# Power_Switch.net
KiCad netlist of a schematic drawn in Altium Designer
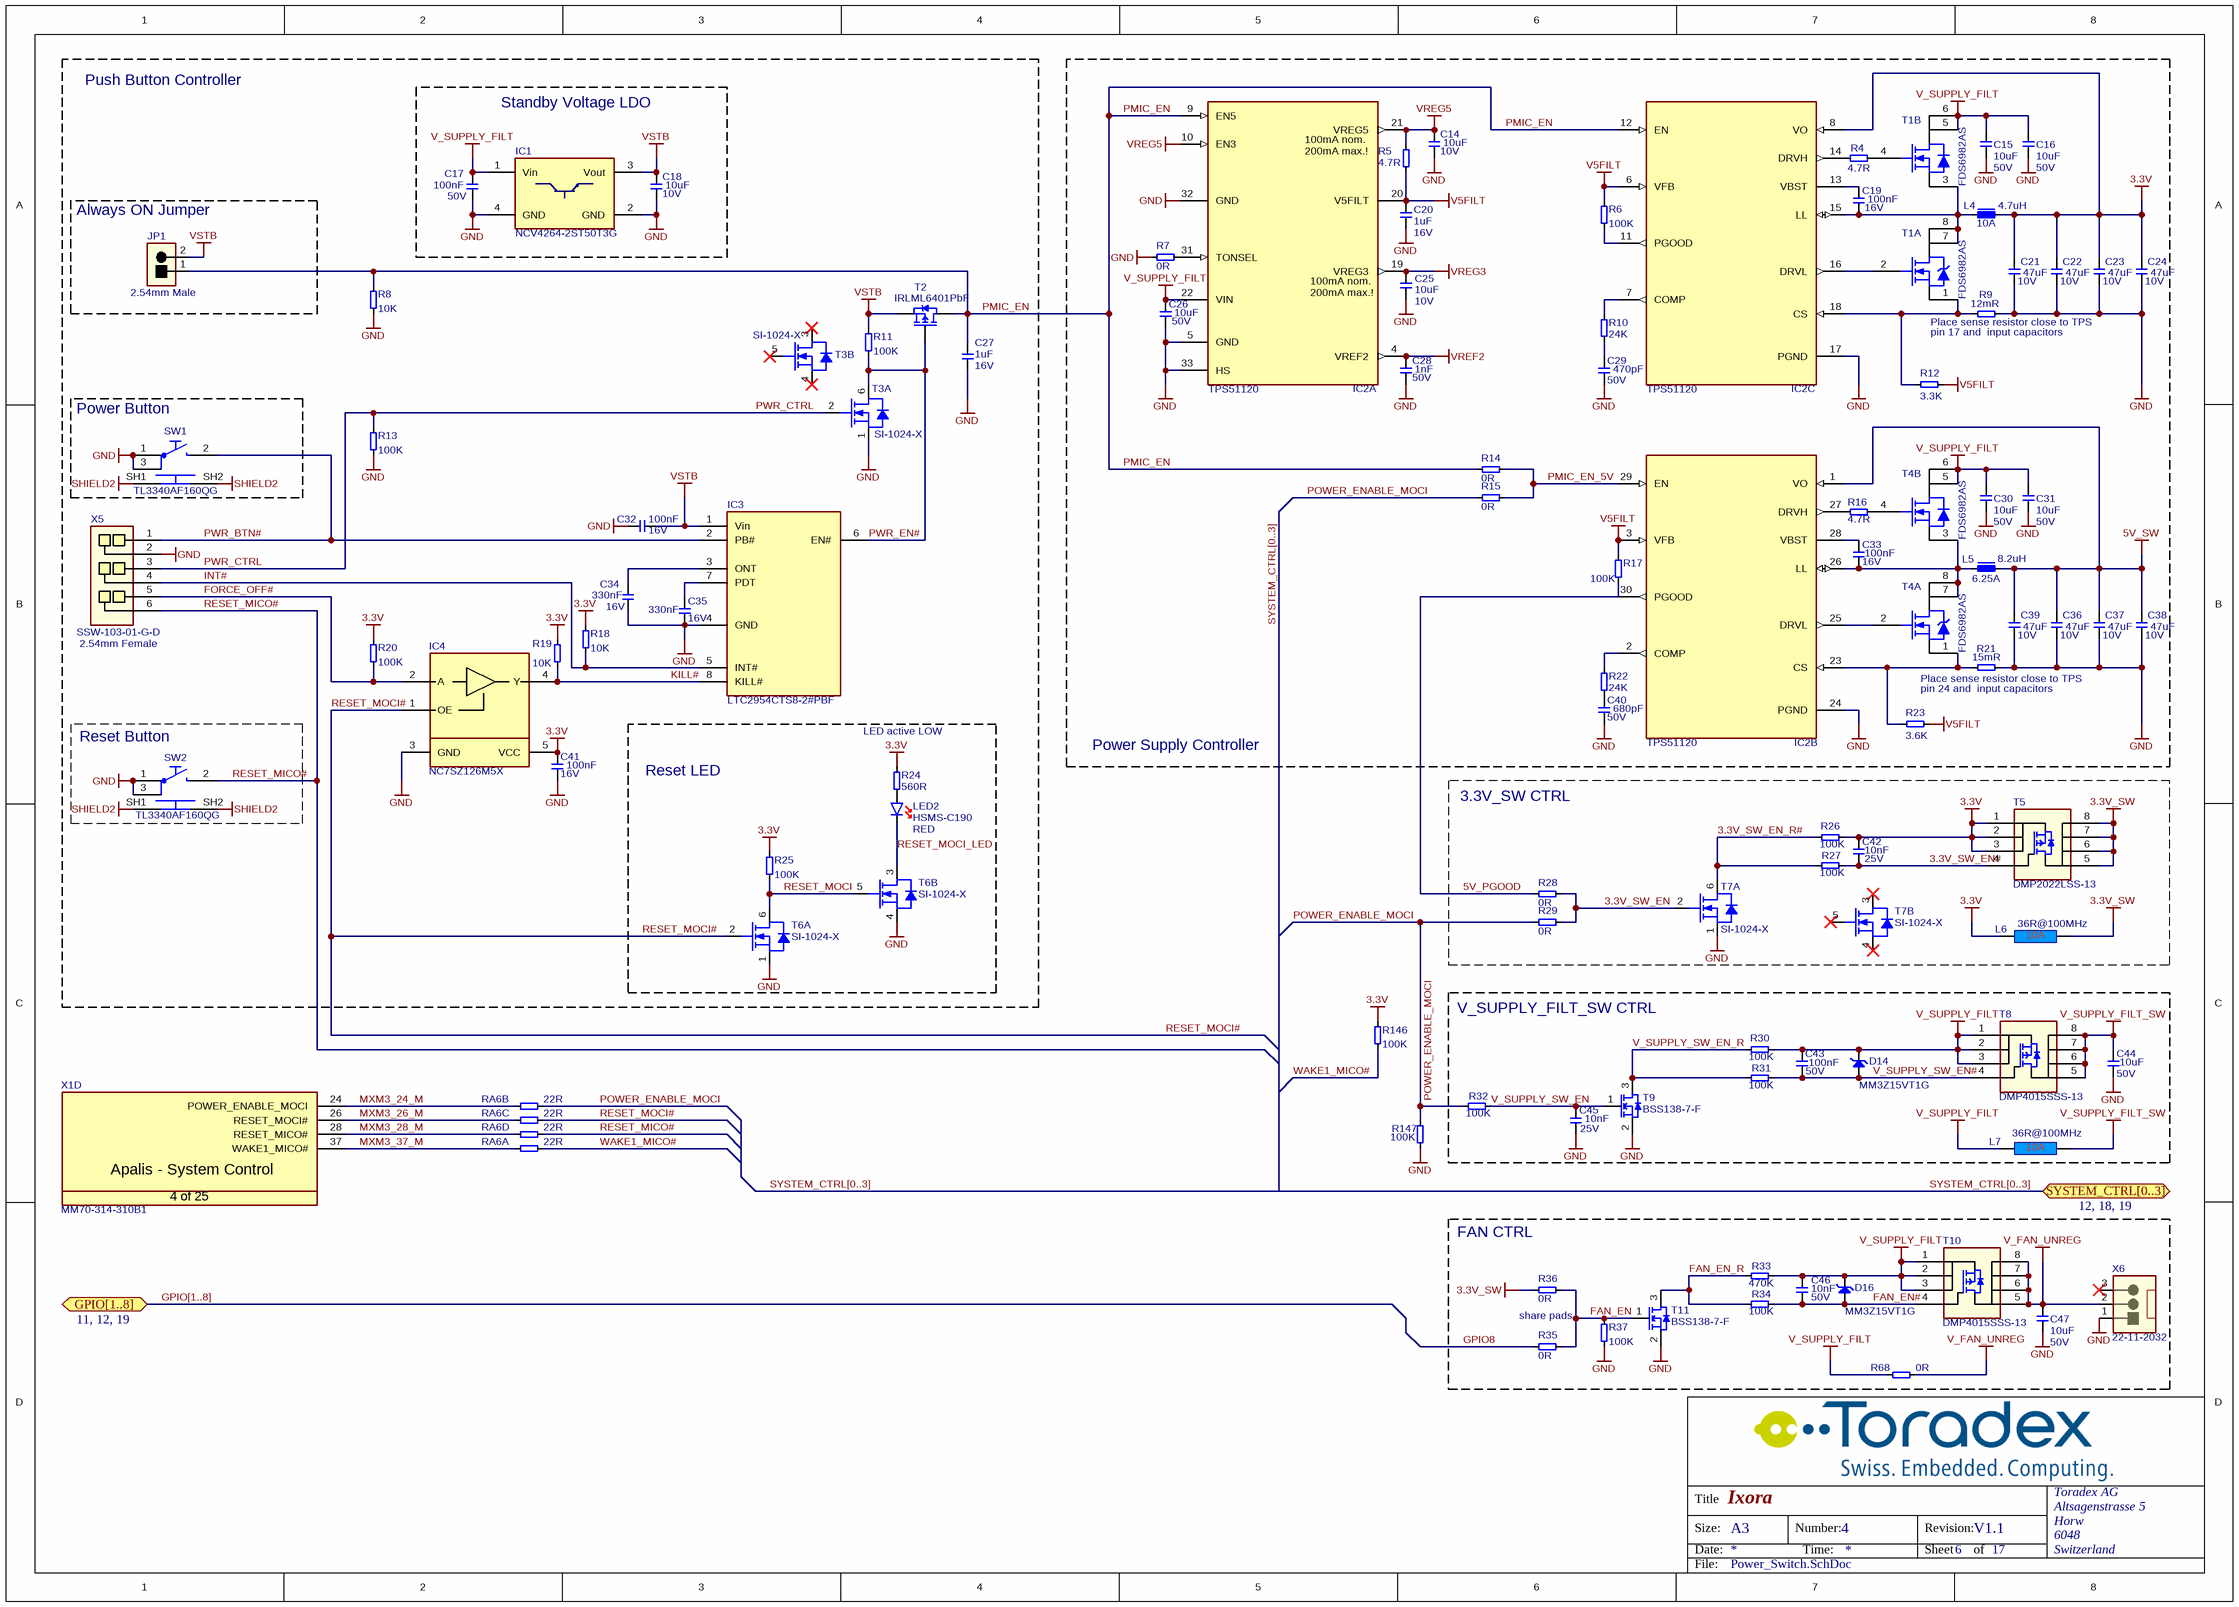
[diagram p0: Power_Switch.SchDoc]

(export (version "E")
  (design (tool "Eeschema 10.0.6"))
  (components
    (comp (ref "C14")
      (value "10uF")
      (footprint "T_CAPC0603X33N")
      (description "Capacitor Ceramic X5R 10uF 10V 20% 0603")
      (fields (field (name "TOLERANCE") "20%") (field (name "RATING") "10V"))
      (libsource (lib "Ixora") (part "C-X5R-10uF-10V-20%-0603"))
    )
    (comp (ref "C15")
      (value "10uF")
      (footprint "CAPC3225X160N")
      (description "Capacitor Ceramic X5R 10uF 50V 20% 1210")
      (fields (field (name "TOLERANCE") "20%") (field (name "RATING") "50V"))
      (libsource (lib "Ixora") (part "C-X5R-10uF-50V-20%-1210"))
    )
    (comp (ref "C16")
      (value "10uF")
      (footprint "CAPC3225X160N")
      (description "Capacitor Ceramic X5R 10uF 50V 20% 1210")
      (fields (field (name "TOLERANCE") "20%") (field (name "RATING") "50V"))
      (libsource (lib "Ixora") (part "C-X5R-10uF-50V-20%-1210"))
    )
    (comp (ref "C17")
      (value "100nF")
      (footprint "T_CAPC0603X33N")
      (description "Capacitor Ceramic X7R 100nF 50V 20% 0603")
      (fields (field (name "TOLERANCE") "20%") (field (name "RATING") "50V"))
      (libsource (lib "Ixora") (part "C-X7R-100nF-50V-20%-0603"))
    )
    (comp (ref "C18")
      (value "10uF")
      (footprint "T_CAPC0603X33N")
      (description "Capacitor Ceramic X5R 10uF 10V 20% 0603")
      (fields (field (name "TOLERANCE") "20%") (field (name "RATING") "10V"))
      (libsource (lib "Ixora") (part "C-X5R-10uF-10V-20%-0603"))
    )
    (comp (ref "C19")
      (value "100nF")
      (footprint "CAPC1005X60N")
      (description "Capacitor Ceramic X7R 100nF 16V 10% 0402")
      (fields (field (name "TOLERANCE") "10%") (field (name "RATING") "16V"))
      (libsource (lib "Ixora") (part "C-X7R-100nF-16V-10%-0402"))
    )
    (comp (ref "C20")
      (value "1uF")
      (footprint "T_CAPC0603X33N")
      (description "Capacitor Ceramic X5R 1uF 16V 20% 0603")
      (fields (field (name "TOLERANCE") "20%") (field (name "RATING") "16V"))
      (libsource (lib "Ixora") (part "C-X5R-1uF-16V-20%-0603"))
    )
    (comp (ref "C21")
      (value "47uF")
      (footprint "T_CAPC0805X125N")
      (description "Capacitor Ceramic X5R 47uF 10V 20% 0805")
      (fields (field (name "TOLERANCE") "20%") (field (name "RATING") "10V"))
      (libsource (lib "Ixora") (part "C-X5R-47uF-10V-20%-0805"))
    )
    (comp (ref "C22")
      (value "47uF")
      (footprint "T_CAPC0805X125N")
      (description "Capacitor Ceramic X5R 47uF 10V 20% 0805")
      (fields (field (name "TOLERANCE") "20%") (field (name "RATING") "10V"))
      (libsource (lib "Ixora") (part "C-X5R-47uF-10V-20%-0805"))
    )
    (comp (ref "C23")
      (value "47uF")
      (footprint "T_CAPC0805X125N")
      (description "Capacitor Ceramic X5R 47uF 10V 20% 0805")
      (fields (field (name "TOLERANCE") "20%") (field (name "RATING") "10V"))
      (libsource (lib "Ixora") (part "C-X5R-47uF-10V-20%-0805"))
    )
    (comp (ref "C24")
      (value "47uF")
      (footprint "T_CAPC0805X125N")
      (description "Capacitor Ceramic X5R 47uF 10V 20% 0805")
      (fields (field (name "TOLERANCE") "20%") (field (name "RATING") "10V"))
      (libsource (lib "Ixora") (part "C-X5R-47uF-10V-20%-0805"))
    )
    (comp (ref "C25")
      (value "10uF")
      (footprint "T_CAPC0603X33N")
      (description "Capacitor Ceramic X5R 10uF 10V 20% 0603")
      (fields (field (name "TOLERANCE") "20%") (field (name "RATING") "10V"))
      (libsource (lib "Ixora") (part "C-X5R-10uF-10V-20%-0603"))
    )
    (comp (ref "C26")
      (value "10uF")
      (footprint "CAPC3225X160N")
      (description "Capacitor Ceramic X5R 10uF 50V 20% 1210")
      (fields (field (name "TOLERANCE") "20%") (field (name "RATING") "50V"))
      (libsource (lib "Ixora") (part "C-X5R-10uF-50V-20%-1210"))
    )
    (comp (ref "C27")
      (value "1uF")
      (footprint "T_CAPC0603X33N")
      (description "Capacitor Ceramic X5R 1uF 16V 20% 0603")
      (fields (field (name "TOLERANCE") "20%") (field (name "RATING") "16V"))
      (libsource (lib "Ixora") (part "C-X5R-1uF-16V-20%-0603"))
    )
    (comp (ref "C28")
      (value "1nF")
      (footprint "CAPC1005X60N")
      (description "Capacitor Ceramic X7R 1nF 50V 10% 0402")
      (fields (field (name "TOLERANCE") "10%") (field (name "RATING") "50V"))
      (libsource (lib "Ixora") (part "C-X7R-1nF-50V-10%-0402"))
    )
    (comp (ref "C29")
      (value "470pF")
      (footprint "CAPC1005X60N")
      (description "Capacitor Ceramic X7R 470pF 50V 10% 0402")
      (fields (field (name "TOLERANCE") "10%") (field (name "RATING") "50V"))
      (libsource (lib "Ixora") (part "C-X7R-470pF-50V-10%-0402"))
    )
    (comp (ref "C30")
      (value "10uF")
      (footprint "CAPC3225X160N")
      (description "Capacitor Ceramic X5R 10uF 50V 20% 1210")
      (fields (field (name "TOLERANCE") "20%") (field (name "RATING") "50V"))
      (libsource (lib "Ixora") (part "C-X5R-10uF-50V-20%-1210"))
    )
    (comp (ref "C31")
      (value "10uF")
      (footprint "CAPC3225X160N")
      (description "Capacitor Ceramic X5R 10uF 50V 20% 1210")
      (fields (field (name "TOLERANCE") "20%") (field (name "RATING") "50V"))
      (libsource (lib "Ixora") (part "C-X5R-10uF-50V-20%-1210"))
    )
    (comp (ref "C32")
      (value "100nF")
      (footprint "CAPC1005X60N")
      (description "Capacitor Ceramic X7R 100nF 16V 10% 0402")
      (fields (field (name "TOLERANCE") "10%") (field (name "RATING") "16V"))
      (libsource (lib "Ixora") (part "C-X7R-100nF-16V-10%-0402"))
    )
    (comp (ref "C33")
      (value "100nF")
      (footprint "CAPC1005X60N")
      (description "Capacitor Ceramic X7R 100nF 16V 10% 0402")
      (fields (field (name "TOLERANCE") "10%") (field (name "RATING") "16V"))
      (libsource (lib "Ixora") (part "C-X7R-100nF-16V-10%-0402"))
    )
    (comp (ref "C34")
      (value "330nF")
      (footprint "T_CAPC0805X125N")
      (description "Capacitor Ceramic X7R 330nF 16V 10% 0805")
      (fields (field (name "TOLERANCE") "10%") (field (name "RATING") "16V"))
      (libsource (lib "Ixora") (part "C-X7R-330nF-16V-10%-0805"))
    )
    (comp (ref "C35")
      (value "330nF")
      (footprint "T_CAPC0805X125N")
      (description "Capacitor Ceramic X7R 330nF 16V 10% 0805")
      (fields (field (name "TOLERANCE") "10%") (field (name "RATING") "16V"))
      (libsource (lib "Ixora") (part "C-X7R-330nF-16V-10%-0805"))
    )
    (comp (ref "C36")
      (value "47uF")
      (footprint "T_CAPC0805X125N")
      (description "Capacitor Ceramic X5R 47uF 10V 20% 0805")
      (fields (field (name "TOLERANCE") "20%") (field (name "RATING") "10V"))
      (libsource (lib "Ixora") (part "C-X5R-47uF-10V-20%-0805"))
    )
    (comp (ref "C37")
      (value "47uF")
      (footprint "T_CAPC0805X125N")
      (description "Capacitor Ceramic X5R 47uF 10V 20% 0805")
      (fields (field (name "TOLERANCE") "20%") (field (name "RATING") "10V"))
      (libsource (lib "Ixora") (part "C-X5R-47uF-10V-20%-0805"))
    )
    (comp (ref "C38")
      (value "47uF")
      (footprint "T_CAPC0805X125N")
      (description "Capacitor Ceramic X5R 47uF 10V 20% 0805")
      (fields (field (name "TOLERANCE") "20%") (field (name "RATING") "10V"))
      (libsource (lib "Ixora") (part "C-X5R-47uF-10V-20%-0805"))
    )
    (comp (ref "C39")
      (value "47uF")
      (footprint "T_CAPC0805X125N")
      (description "Capacitor Ceramic X5R 47uF 10V 20% 0805")
      (fields (field (name "TOLERANCE") "20%") (field (name "RATING") "10V"))
      (libsource (lib "Ixora") (part "C-X5R-47uF-10V-20%-0805"))
    )
    (comp (ref "C40")
      (value "680pF")
      (footprint "CAPC1005X60N")
      (description "Capacitor Ceramic X7R 680pF 50V 10% 0402")
      (fields (field (name "TOLERANCE") "10%") (field (name "RATING") "50V"))
      (libsource (lib "Ixora") (part "C-X7R-680pF-50V-10%-0402"))
    )
    (comp (ref "C41")
      (value "100nF")
      (footprint "CAPC1005X60N")
      (description "Capacitor Ceramic X7R 100nF 16V 10% 0402")
      (fields (field (name "TOLERANCE") "10%") (field (name "RATING") "16V"))
      (libsource (lib "Ixora") (part "C-X7R-100nF-16V-10%-0402"))
    )
    (comp (ref "C42")
      (value "10nF")
      (footprint "CAPC1005X60N")
      (description "Capacitor Ceramic X7R 10nF 25V 10% 0402")
      (fields (field (name "TOLERANCE") "10%") (field (name "RATING") "25V"))
      (libsource (lib "Ixora") (part "C-X7R-10nF-25V-10%-0402"))
    )
    (comp (ref "C43")
      (value "100nF")
      (footprint "T_CAPC0603X33N")
      (description "Capacitor Ceramic X7R 100nF 50V 20% 0603")
      (fields (field (name "TOLERANCE") "20%") (field (name "RATING") "50V"))
      (libsource (lib "Ixora") (part "C-X7R-100nF-50V-20%-0603"))
    )
    (comp (ref "C44")
      (value "10uF")
      (footprint "CAPC3225X160N")
      (description "Capacitor Ceramic X5R 10uF 50V 20% 1210")
      (fields (field (name "TOLERANCE") "20%") (field (name "RATING") "50V"))
      (libsource (lib "Ixora") (part "C-X5R-10uF-50V-20%-1210"))
    )
    (comp (ref "C45")
      (value "10nF")
      (footprint "CAPC1005X60N")
      (description "Capacitor Ceramic X7R 10nF 25V 10% 0402")
      (fields (field (name "TOLERANCE") "10%") (field (name "RATING") "25V"))
      (libsource (lib "Ixora") (part "C-X7R-10nF-25V-10%-0402"))
    )
    (comp (ref "C46")
      (value "10nF")
      (footprint "CAPC1005X60N")
      (description "Capacitor Ceramic X7R 10nF 50V 10% 0402")
      (fields (field (name "TOLERANCE") "10%") (field (name "RATING") "50V"))
      (libsource (lib "Ixora") (part "C-X7R-10nF-50V-10%-0402"))
    )
    (comp (ref "C47")
      (value "10uF")
      (footprint "CAPC3225X160N")
      (description "Capacitor Ceramic X5R 10uF 50V 20% 1210")
      (fields (field (name "TOLERANCE") "20%") (field (name "RATING") "50V"))
      (libsource (lib "Ixora") (part "C-X5R-10uF-50V-20%-1210"))
    )
    (comp (ref "D14")
      (value "MM3Z15VT1G")
      (footprint "T_SOD-323")
      (description "Zener Diode, Vz=15V, 300mW, SOD-323")
      (fields (field (name "MANUFACTURER PART NO.") "MM3Z15VT1G"))
      (libsource (lib "Ixora") (part "D-OnSemi-MM3Z15VT1G"))
    )
    (comp (ref "D16")
      (value "MM3Z15VT1G")
      (footprint "T_SOD-323")
      (description "Zener Diode, Vz=15V, 300mW, SOD-323")
      (fields (field (name "MANUFACTURER PART NO.") "MM3Z15VT1G"))
      (libsource (lib "Ixora") (part "D-OnSemi-MM3Z15VT1G"))
    )
    (comp (ref "IC1")
      (value "NCV4264-2ST50T3G")
      (footprint "T_ON_NCV4264-2ST50T3G")
      (description "NCV4264-2ST50T3G LDO Regulator")
      (fields (field (name "MANUFACTURER PART NO.") "NCV4264-2ST50T3G"))
      (libsource (lib "Ixora") (part "IC-ON-NCV4264-2ST50T3G"))
    )
    (comp (ref "IC2")
      (value "TPS51120")
      (footprint "QFN50P500X500X100-33N")
      (description "Power Supply Controller")
      (fields (field (name "MANUFACTURER PART NO.") "TPS51120"))
      (libsource (lib "Ixora") (part "IC-TI-TPS51120"))
    )
    (comp (ref "IC3")
      (value "LTC2954CTS8-2#PBF")
      (footprint "T_LINEAR_LTC2954CTS8-2#PBF")
      (description "Push Button On/Off Controller")
      (fields (field (name "MANUFACTURER PART NO.") "LTC2954CTS8-2#PBF"))
      (libsource (lib "Ixora") (part "IC-LIN-LTC2954CTS8-2#PBF"))
    )
    (comp (ref "IC4")
      (value "NC7SZ126M5X")
      (footprint "SOT95P279X142-5N")
      (description "NC7SZ126M5X  Buffer Three-State Output")
      (fields (field (name "MANUFACTURER PART NO.") "NC7SZ126M5X"))
      (libsource (lib "Ixora") (part "IC-FAR-NC7SZ126M5X"))
    )
    (comp (ref "JP1")
      (value "TSW-101-07-G-D")
      (footprint "T_Samtec_TSW-101-07-G-D")
      (description "Header male, 1x2 Pins, 2.54 mm pitch")
      (libsource (lib "Ixora") (part "CON-Samtec-TSW-101-07-G-D"))
    )
    (comp (ref "L4")
      (value "4.7uH")
      (footprint "T_INDM110100")
      (description "Inductance 4.7uH 10A 20% 15.5 mOhm -40°C to125°C")
      (fields
        (field (name "TOLERANCE") "20%")
        (field (name "MANUFACTURER PART NO.") "SRP1038A-4R7M")
        (field (name "RATING") "10A")
      )
      (libsource (lib "Ixora") (part "L-Bourns-SRP1038A-4R7M"))
    )
    (comp (ref "L5")
      (value "8.2uH")
      (footprint "T_INDM120120X80N")
      (description "Inductance 8.2uH 6.25A 20%")
      (fields
        (field (name "TOLERANCE") "20%")
        (field (name "MANUFACTURER PART NO.") "744771008")
        (field (name "RATING") "6.25A")
      )
      (libsource (lib "Ixora") (part "L-Wurth-744771008-8.2uH-6.25A-20%"))
    )
    (comp (ref "L6")
      (value "36R@100MHz")
      (footprint "T_Laird_35F0121-0SR-10")
      (description "Power Supply FB 10A")
      (fields (field (name "TOLERANCE") "25%"))
      (libsource (lib "Ixora") (part "L-Laird-35F0121-0SR-10-10A-25%"))
    )
    (comp (ref "L7")
      (value "36R@100MHz")
      (footprint "T_Laird_35F0121-0SR-10")
      (description "Power Supply FB 10A")
      (fields (field (name "TOLERANCE") "25%"))
      (libsource (lib "Ixora") (part "L-Laird-35F0121-0SR-10-10A-25%"))
    )
    (comp (ref "LED2")
      (value "LED")
      (footprint "LEDC1608X80N_R")
      (description "Surface mount LED red 20mA")
      (fields (field (name "MANUFACTURER PART NO.") "HSMS-C190") (field (name "COLOR") "RED"))
      (libsource (lib "Ixora") (part "LED-Avago-HSMS-C190"))
    )
    (comp (ref "R4")
      (value "4.7R")
      (footprint "RESC1005X40N")
      (description "Resistor 4.7 ohm 63mW 5% 0402")
      (fields (field (name "TOLERANCE") "5%"))
      (libsource (lib "Ixora") (part "R-4.7R-63mW-5%-0402"))
    )
    (comp (ref "R5")
      (value "4.7R")
      (footprint "RESC1005X40N")
      (description "Resistor 4.7 ohm 63mW 5% 0402")
      (fields (field (name "TOLERANCE") "5%"))
      (libsource (lib "Ixora") (part "R-4.7R-63mW-5%-0402"))
    )
    (comp (ref "R6")
      (value "100K")
      (footprint "RESC1005X40N")
      (description "Resistor 100 Kohm 63mW 5% 0402")
      (fields (field (name "TOLERANCE") "5%"))
      (libsource (lib "Ixora") (part "R-100KR-63mW-5%-0402"))
    )
    (comp (ref "R7")
      (value "0R")
      (footprint "RESC1005X40N")
      (description "Resistor 0 ohm 63mW 1% 0402")
      (fields (field (name "TOLERANCE") "1%"))
      (libsource (lib "Ixora") (part "R-0R-63mW-1%-0402"))
    )
    (comp (ref "R8")
      (value "10K")
      (footprint "RESC1005X40N")
      (description "Resistor 10 Kohm 63mW 5% 0402")
      (fields (field (name "TOLERANCE") "5%"))
      (libsource (lib "Ixora") (part "R-10KR-63mW-5%-0402"))
    )
    (comp (ref "R9")
      (value "12mR")
      (footprint "RESC3316X76N")
      (description "Resistor 12 mohm 250mW 1% 1206")
      (fields (field (name "TOLERANCE") "1%"))
      (libsource (lib "Ixora") (part "R-12mR-250mW-1%-1206"))
    )
    (comp (ref "R10")
      (value "24K")
      (footprint "RESC1005X40N")
      (description "Resistor 24 Kohm 63mW 1% 0402")
      (fields (field (name "TOLERANCE") "1%"))
      (libsource (lib "Ixora") (part "R-24KR-63mW-1%-0402"))
    )
    (comp (ref "R11")
      (value "100K")
      (footprint "RESC1005X40N")
      (description "Resistor 100 Kohm 63mW 5% 0402")
      (fields (field (name "TOLERANCE") "5%"))
      (libsource (lib "Ixora") (part "R-100KR-63mW-5%-0402"))
    )
    (comp (ref "R12")
      (value "3.3K")
      (footprint "RESC1005X40N")
      (description "Resistor 3.3 Kohm 63mW 1% 0402")
      (fields (field (name "TOLERANCE") "1%"))
      (libsource (lib "Ixora") (part "R-3.3KR-63mW-1%-0402"))
    )
    (comp (ref "R13")
      (value "100K")
      (footprint "RESC1005X40N")
      (description "Resistor 100 Kohm 63mW 5% 0402")
      (fields (field (name "TOLERANCE") "5%"))
      (libsource (lib "Ixora") (part "R-100KR-63mW-5%-0402"))
    )
    (comp (ref "R14")
      (value "0R")
      (footprint "T_RESC0603X30N")
      (description "Resistor 0 ohm 63mW 1% 0603")
      (fields (field (name "TOLERANCE") "1%"))
      (libsource (lib "Ixora") (part "R-0R-63mW-1%-0603"))
    )
    (comp (ref "R15")
      (value "0R")
      (footprint "T_RESC0603X30N")
      (description "Resistor 0 ohm 63mW 1% 0603")
      (fields (field (name "TOLERANCE") "1%"))
      (libsource (lib "Ixora") (part "R-0R-63mW-1%-0603"))
    )
    (comp (ref "R16")
      (value "4.7R")
      (footprint "RESC1005X40N")
      (description "Resistor 4.7 ohm 63mW 5% 0402")
      (fields (field (name "TOLERANCE") "5%"))
      (libsource (lib "Ixora") (part "R-4.7R-63mW-5%-0402"))
    )
    (comp (ref "R17")
      (value "100K")
      (footprint "RESC1005X40N")
      (description "Resistor 100 Kohm 63mW 5% 0402")
      (fields (field (name "TOLERANCE") "5%"))
      (libsource (lib "Ixora") (part "R-100KR-63mW-5%-0402"))
    )
    (comp (ref "R18")
      (value "10K")
      (footprint "RESC1005X40N")
      (description "Resistor 10 Kohm 63mW 5% 0402")
      (fields (field (name "TOLERANCE") "5%"))
      (libsource (lib "Ixora") (part "R-10KR-63mW-5%-0402"))
    )
    (comp (ref "R19")
      (value "10K")
      (footprint "RESC1005X40N")
      (description "Resistor 10 Kohm 63mW 5% 0402")
      (fields (field (name "TOLERANCE") "5%"))
      (libsource (lib "Ixora") (part "R-10KR-63mW-5%-0402"))
    )
    (comp (ref "R20")
      (value "100K")
      (footprint "RESC1005X40N")
      (description "Resistor 100 Kohm 63mW 5% 0402")
      (fields (field (name "TOLERANCE") "5%"))
      (libsource (lib "Ixora") (part "R-100KR-63mW-5%-0402"))
    )
    (comp (ref "R21")
      (value "15mR")
      (footprint "RESC3316X76N")
      (description "Resistor 15 mohm 250mW 1% 1206")
      (fields (field (name "TOLERANCE") "1%"))
      (libsource (lib "Ixora") (part "R-15mR-250mW-1%-1206"))
    )
    (comp (ref "R22")
      (value "24K")
      (footprint "RESC1005X40N")
      (description "Resistor 24 Kohm 63mW 1% 0402")
      (fields (field (name "TOLERANCE") "1%"))
      (libsource (lib "Ixora") (part "R-24KR-63mW-1%-0402"))
    )
    (comp (ref "R23")
      (value "3.6K")
      (footprint "RESC1005X40N")
      (description "Resistor 3.6 Kohm 63mW 1% 0402")
      (fields (field (name "TOLERANCE") "1%"))
      (libsource (lib "Ixora") (part "R-3.6KR-63mW-1%-0402"))
    )
    (comp (ref "R24")
      (value "560R")
      (footprint "RESC1005X40N")
      (description "Resistor 560 ohm 63mW 5% 0402")
      (fields (field (name "TOLERANCE") "5%"))
      (libsource (lib "Ixora") (part "R-560R-63mW-5%-0402"))
    )
    (comp (ref "R25")
      (value "100K")
      (footprint "RESC1005X40N")
      (description "Resistor 100 Kohm 63mW 5% 0402")
      (fields (field (name "TOLERANCE") "5%"))
      (libsource (lib "Ixora") (part "R-100KR-63mW-5%-0402"))
    )
    (comp (ref "R26")
      (value "100K")
      (footprint "RESC1005X40N")
      (description "Resistor 100 Kohm 63mW 5% 0402")
      (fields (field (name "TOLERANCE") "5%"))
      (libsource (lib "Ixora") (part "R-100KR-63mW-5%-0402"))
    )
    (comp (ref "R27")
      (value "100K")
      (footprint "RESC1005X40N")
      (description "Resistor 100 Kohm 63mW 5% 0402")
      (fields (field (name "TOLERANCE") "5%"))
      (libsource (lib "Ixora") (part "R-100KR-63mW-5%-0402"))
    )
    (comp (ref "R28")
      (value "0R")
      (footprint "T_RESC0603X30N")
      (description "Resistor 0 ohm 63mW 1% 0603")
      (fields (field (name "TOLERANCE") "1%"))
      (libsource (lib "Ixora") (part "R-0R-63mW-1%-0603"))
    )
    (comp (ref "R29")
      (value "0R")
      (footprint "T_RESC0603X30N")
      (description "Resistor 0 ohm 63mW 1% 0603")
      (fields (field (name "TOLERANCE") "1%"))
      (libsource (lib "Ixora") (part "R-0R-63mW-1%-0603"))
    )
    (comp (ref "R30")
      (value "100K")
      (footprint "RESC1005X40N")
      (description "Resistor 100 Kohm 63mW 5% 0402")
      (fields (field (name "TOLERANCE") "5%"))
      (libsource (lib "Ixora") (part "R-100KR-63mW-5%-0402"))
    )
    (comp (ref "R31")
      (value "100K")
      (footprint "RESC1005X40N")
      (description "Resistor 100 Kohm 63mW 5% 0402")
      (fields (field (name "TOLERANCE") "5%"))
      (libsource (lib "Ixora") (part "R-100KR-63mW-5%-0402"))
    )
    (comp (ref "R32")
      (value "100K")
      (footprint "RESC1005X40N")
      (description "Resistor 100 Kohm 63mW 5% 0402")
      (fields (field (name "TOLERANCE") "5%"))
      (libsource (lib "Ixora") (part "R-100KR-63mW-5%-0402"))
    )
    (comp (ref "R33")
      (value "470K")
      (footprint "RESC1005X40N")
      (description "Resistor 470 Kohm 63mW 5% 0402")
      (fields (field (name "TOLERANCE") "5%"))
      (libsource (lib "Ixora") (part "R-470KR-63mW-5%-0402"))
    )
    (comp (ref "R34")
      (value "100K")
      (footprint "RESC1005X40N")
      (description "Resistor 100 Kohm 63mW 5% 0402")
      (fields (field (name "TOLERANCE") "5%"))
      (libsource (lib "Ixora") (part "R-100KR-63mW-5%-0402"))
    )
    (comp (ref "R35")
      (value "0R")
      (footprint "T_RESC0603X30N")
      (description "Resistor 0 ohm 63mW 1% 0603")
      (fields (field (name "TOLERANCE") "1%"))
      (libsource (lib "Ixora") (part "R-0R-63mW-1%-0603"))
    )
    (comp (ref "R36")
      (value "0R")
      (footprint "T_RESC0603X30N")
      (description "Resistor 0 ohm 63mW 1% 0603")
      (fields (field (name "TOLERANCE") "1%"))
      (libsource (lib "Ixora") (part "R-0R-63mW-1%-0603"))
    )
    (comp (ref "R37")
      (value "100K")
      (footprint "RESC1005X40N")
      (description "Resistor 100 Kohm 63mW 5% 0402")
      (fields (field (name "TOLERANCE") "5%"))
      (libsource (lib "Ixora") (part "R-100KR-63mW-5%-0402"))
    )
    (comp (ref "R68")
      (value "0R")
      (footprint "T_RESC3225X30N")
      (description "Resistor 0 ohm 63mW 1% 1210")
      (fields (field (name "TOLERANCE") "1%"))
      (libsource (lib "Ixora") (part "R-0R-63mW-1%-1210"))
    )
    (comp (ref "R146")
      (value "100K")
      (footprint "RESC1005X40N")
      (description "Resistor 100 Kohm 63mW 5% 0402")
      (fields (field (name "TOLERANCE") "5%"))
      (libsource (lib "Ixora") (part "R-100KR-63mW-5%-0402"))
    )
    (comp (ref "R147")
      (value "100K")
      (footprint "RESC1005X40N")
      (description "Resistor 100 Kohm 63mW 5% 0402")
      (fields (field (name "TOLERANCE") "5%"))
      (libsource (lib "") (part "R-100KR-63mW-5%-0402_1"))
    )
    (comp (ref "RA6")
      (value "22R")
      (footprint "T_Resistor_Array_X4")
      (description "Resistor Array 22 R 63mW 5% 1206")
      (fields (field (name "TOLERANCE") "5%"))
      (libsource (lib "Ixora") (part "RA-22R-63mW-5%-1206-div"))
    )
    (comp (ref "SW1")
      (value "TL3340AF160QG")
      (footprint "T_E-SWITCH- TL3340AF160QG")
      (description "SWITCH TACT SUB MINI 160GF SMD Right Angle")
      (fields (field (name "MANUFACTURER PART NO.") "TL3340AF160QG"))
      (libsource (lib "Ixora") (part "SW-E-Switch-TL3340AF160QG"))
    )
    (comp (ref "SW2")
      (value "TL3340AF160QG")
      (footprint "T_E-SWITCH- TL3340AF160QG")
      (description "SWITCH TACT SUB MINI 160GF SMD Right Angle")
      (fields (field (name "MANUFACTURER PART NO.") "TL3340AF160QG"))
      (libsource (lib "Ixora") (part "SW-E-Switch-TL3340AF160QG"))
    )
    (comp (ref "T1")
      (value "FDS6982AS")
      (footprint "SOIC127P600X173-8N")
      (description "N-Channel PowerTrench SyncFET")
      (fields (field (name "MANUFACTURER PART NO.") "FDS6982AS"))
      (libsource (lib "Ixora") (part "T-Fairchild-FDS6982AS-N"))
    )
    (comp (ref "T2")
      (value "IRLML6401PbF")
      (footprint "SOT95P237X112-3N")
      (description "p-channel MOSFET, IRLML6401PbF")
      (libsource (lib "Ixora") (part "T-IR-IRLML6401PbF-SOT-23"))
    )
    (comp (ref "T3")
      (value "T-Vishay-SI-1024X-N")
      (footprint "SOTFL50P160X60-6N")
      (description "Dual N-Channel 20V (D-S)  MOSFET")
      (fields (field (name "MANUFACTURER PART NO.") "SI-1024-X"))
      (libsource (lib "Ixora") (part "T-Vishay-SI-1024X-N"))
    )
    (comp (ref "T4")
      (value "FDS6982AS")
      (footprint "SOIC127P600X173-8N")
      (description "N-Channel PowerTrench SyncFET")
      (fields (field (name "MANUFACTURER PART NO.") "FDS6982AS"))
      (libsource (lib "Ixora") (part "T-Fairchild-FDS6982AS-N"))
    )
    (comp (ref "T5")
      (value "DMP2022LSS-13")
      (footprint "SOIC127P600X173-8N")
      (description "p-channel MOSFET, DMP2022LSS-13")
      (fields (field (name "MANUFACTURER PART NO.") "DMP2022LSS-13"))
      (libsource (lib "Ixora") (part "T-Diodes-DMP2022LSS-13-8-SOIC"))
    )
    (comp (ref "T6")
      (value "T-Vishay-SI-1024X-N")
      (footprint "SOTFL50P160X60-6N")
      (description "Dual N-Channel 20V (D-S)  MOSFET")
      (fields (field (name "MANUFACTURER PART NO.") "SI-1024-X"))
      (libsource (lib "Ixora") (part "T-Vishay-SI-1024X-N"))
    )
    (comp (ref "T7")
      (value "T-Vishay-SI-1024X-N")
      (footprint "SOTFL50P160X60-6N")
      (description "Dual N-Channel 20V (D-S)  MOSFET")
      (fields (field (name "MANUFACTURER PART NO.") "SI-1024-X"))
      (libsource (lib "Ixora") (part "T-Vishay-SI-1024X-N"))
    )
    (comp (ref "T8")
      (value "DMP4015SSS-13")
      (footprint "SOIC127P600X173-8N")
      (description "P-channel MOSFET, DMP4015SSS-13")
      (fields (field (name "MANUFACTURER PART NO.") "DMP4015SSS-13"))
      (libsource (lib "Ixora") (part "T-DiodesInc-DMP4015SSS-13"))
    )
    (comp (ref "T9")
      (value "BSS138-7-F")
      (footprint "SOT95P237X112-3N")
      (description "N-channel MOSFET, BSS138-7-F")
      (fields (field (name "MANUFACTURER PART NO.") "BSS138-7-F"))
      (libsource (lib "Ixora") (part "T-Diodes-BSS138-7-F"))
    )
    (comp (ref "T10")
      (value "DMP4015SSS-13")
      (footprint "SOIC127P600X173-8N")
      (description "P-channel MOSFET, DMP4015SSS-13")
      (fields (field (name "MANUFACTURER PART NO.") "DMP4015SSS-13"))
      (libsource (lib "Ixora") (part "T-DiodesInc-DMP4015SSS-13"))
    )
    (comp (ref "T11")
      (value "BSS138-7-F")
      (footprint "SOT95P237X112-3N")
      (description "N-channel MOSFET, BSS138-7-F")
      (fields (field (name "MANUFACTURER PART NO.") "BSS138-7-F"))
      (libsource (lib "Ixora") (part "T-Diodes-BSS138-7-F"))
    )
    (comp (ref "X1")
      (value "CON-JAE-MM70-314-310B1-314-0.5mm")
      (footprint "T_JAE_MM70-314-310B1")
      (description "MXM3 Connector")
      (fields (field (name "MANUFACTURER PART NO.") "MM70-314-310B1"))
      (libsource (lib "Ixora") (part "CON-JAE-MM70-314-310B1-314-0.5mm"))
    )
    (comp (ref "X5")
      (value "TSW-103-01-G-D")
      (footprint "T_Samtec_SSW-103-01-G-D")
      (description "Receptacle Female Socket, 2x3 Pins, 2.54mm pitch")
      (fields (field (name "MANUFACTURER PART NO.") "SSW-103-01-G-D"))
      (libsource (lib "Ixora") (part "CON-Samtec-SSW-103-01-G-D"))
    )
    (comp (ref "X6")
      (value "22-11-2032")
      (footprint "T_MOLEX_22-11-2032")
      (description "Header with Friction Lock")
      (fields (field (name "MANUFACTURER PART NO.") "22-11-2032"))
      (libsource (lib "Ixora") (part "CON-Molex-22-11-2032"))
    )
  )
  (nets
    (net (code "12") (name "/3.3V_SW_EN") (class "Default")
      (node (ref "R28") (pin "1") (pinfunction "1_1") (pintype "passive"))
      (node (ref "R29") (pin "2") (pinfunction "2_2") (pintype "passive"))
      (node (ref "T7") (pin "2") (pinfunction "G_2") (pintype "passive"))
    )
    (net (code "13") (name "/3.3V_SW_EN#") (class "Default")
      (node (ref "C42") (pin "1") (pinfunction "1_1") (pintype "passive"))
      (node (ref "R27") (pin "1") (pinfunction "1_1") (pintype "passive"))
      (node (ref "T5") (pin "4") (pinfunction "G_4") (pintype "passive"))
    )
    (net (code "14") (name "/3.3V_SW_EN_R#") (class "Default")
      (node (ref "R26") (pin "2") (pinfunction "2_2") (pintype "passive"))
      (node (ref "R27") (pin "2") (pinfunction "2_2") (pintype "passive"))
      (node (ref "T7") (pin "6") (pinfunction "D_6") (pintype "passive"))
    )
    (net (code "15") (name "/5V_PGOOD") (class "Default")
      (node (ref "IC2") (pin "30") (pinfunction "PGOOD_30") (pintype "output"))
      (node (ref "R17") (pin "1") (pinfunction "1_1") (pintype "passive"))
      (node (ref "R28") (pin "2") (pinfunction "2_2") (pintype "passive"))
    )
    (net (code "16") (name "/FAN_EN") (class "Default")
      (node (ref "R35") (pin "1") (pinfunction "1_1") (pintype "passive"))
      (node (ref "R36") (pin "2") (pinfunction "2_2") (pintype "passive"))
      (node (ref "R37") (pin "1") (pinfunction "1_1") (pintype "passive"))
      (node (ref "T11") (pin "1") (pinfunction "1_1") (pintype "passive"))
    )
    (net (code "17") (name "/FAN_EN#") (class "Default")
      (node (ref "C46") (pin "1") (pinfunction "1_1") (pintype "passive"))
      (node (ref "D16") (pin "2") (pinfunction "A_2") (pintype "power_in"))
      (node (ref "R34") (pin "2") (pinfunction "2_2") (pintype "passive"))
      (node (ref "T10") (pin "4") (pinfunction "G_4") (pintype "passive"))
    )
    (net (code "18") (name "/FAN_EN_R") (class "Default")
      (node (ref "R33") (pin "1") (pinfunction "1_1") (pintype "passive"))
      (node (ref "R34") (pin "1") (pinfunction "1_1") (pintype "passive"))
      (node (ref "T11") (pin "3") (pinfunction "3_3") (pintype "passive"))
    )
    (net (code "19") (name "/FORCE_OFF#") (class "Default")
      (node (ref "IC4") (pin "2") (pinfunction "A_2") (pintype "passive"))
      (node (ref "R20") (pin "1") (pinfunction "1_1") (pintype "passive"))
      (node (ref "X5") (pin "5") (pinfunction "5_5") (pintype "passive"))
    )
    (net (code "20") (name "/GPIO8") (class "Default")
      (node (ref "R35") (pin "2") (pinfunction "2_2") (pintype "passive"))
    )
    (net (code "22") (name "/INT#") (class "Default")
      (node (ref "IC3") (pin "5") (pinfunction "INT#_5") (pintype "passive"))
      (node (ref "R18") (pin "2") (pinfunction "2_2") (pintype "passive"))
      (node (ref "X5") (pin "4") (pinfunction "4_4") (pintype "passive"))
    )
    (net (code "23") (name "/KILL#") (class "Default")
      (node (ref "IC3") (pin "8") (pinfunction "KILL#_8") (pintype "passive"))
      (node (ref "IC4") (pin "4") (pinfunction "Y_4") (pintype "passive"))
      (node (ref "R19") (pin "2") (pinfunction "2_2") (pintype "passive"))
    )
    (net (code "24") (name "/MXM3_24_M") (class "Default")
      (node (ref "RA6") (pin "2") (pinfunction "2_2") (pintype "passive"))
      (node (ref "X1") (pin "24") (pinfunction "POWER_ENABLE_MOCI_24") (pintype "passive"))
    )
    (net (code "25") (name "/MXM3_26_M") (class "Default")
      (node (ref "RA6") (pin "3") (pinfunction "3_3") (pintype "passive"))
      (node (ref "X1") (pin "26") (pinfunction "RESET_MOCI#_26") (pintype "passive"))
    )
    (net (code "26") (name "/MXM3_28_M") (class "Default")
      (node (ref "RA6") (pin "4") (pinfunction "4_4") (pintype "passive"))
      (node (ref "X1") (pin "28") (pinfunction "RESET_MICO#_28") (pintype "passive"))
    )
    (net (code "27") (name "/MXM3_37_M") (class "Default")
      (node (ref "RA6") (pin "1") (pinfunction "1_1") (pintype "passive"))
      (node (ref "X1") (pin "37") (pinfunction "WAKE1_MICO#_37") (pintype "passive"))
    )
    (net (code "28") (name "/PMIC_EN") (class "Default")
      (node (ref "C27") (pin "2") (pinfunction "2_2") (pintype "passive"))
      (node (ref "IC2") (pin "12") (pinfunction "EN_12") (pintype "input"))
      (node (ref "IC2") (pin "9") (pinfunction "EN5_9") (pintype "input"))
      (node (ref "JP1") (pin "1") (pinfunction "1_1") (pintype "passive"))
      (node (ref "R14") (pin "1") (pinfunction "1_1") (pintype "passive"))
      (node (ref "R8") (pin "2") (pinfunction "2_2") (pintype "passive"))
      (node (ref "T2") (pin "3") (pinfunction "3_3") (pintype "passive"))
    )
    (net (code "29") (name "/PMIC_EN_5V") (class "Default")
      (node (ref "IC2") (pin "29") (pinfunction "EN_29") (pintype "input"))
      (node (ref "R14") (pin "2") (pinfunction "2_2") (pintype "passive"))
      (node (ref "R15") (pin "2") (pinfunction "2_2") (pintype "passive"))
    )
    (net (code "30") (name "/POWER_ENABLE_MOCI") (class "Default")
      (node (ref "R147") (pin "2") (pinfunction "2_2") (pintype "passive"))
      (node (ref "R15") (pin "1") (pinfunction "1_1") (pintype "passive"))
      (node (ref "R29") (pin "1") (pinfunction "1_1") (pintype "passive"))
      (node (ref "R32") (pin "1") (pinfunction "1_1") (pintype "passive"))
      (node (ref "RA6") (pin "6") (pinfunction "6_6") (pintype "passive"))
    )
    (net (code "31") (name "/PWR_BTN#") (class "Default")
      (node (ref "IC3") (pin "2") (pinfunction "PB#_2") (pintype "passive"))
      (node (ref "SW1") (pin "2") (pinfunction "2_2") (pintype "passive"))
      (node (ref "X5") (pin "1") (pinfunction "1_1") (pintype "passive"))
    )
    (net (code "32") (name "/PWR_CTRL") (class "Default")
      (node (ref "R13") (pin "2") (pinfunction "2_2") (pintype "passive"))
      (node (ref "T3") (pin "2") (pinfunction "G_2") (pintype "passive"))
      (node (ref "X5") (pin "3") (pinfunction "3_3") (pintype "passive"))
    )
    (net (code "33") (name "/PWR_EN#") (class "Default")
      (node (ref "IC3") (pin "6") (pinfunction "EN#_6") (pintype "passive"))
      (node (ref "R11") (pin "1") (pinfunction "1_1") (pintype "passive"))
      (node (ref "T2") (pin "1") (pinfunction "1_1") (pintype "passive"))
      (node (ref "T3") (pin "6") (pinfunction "D_6") (pintype "passive"))
    )
    (net (code "34") (name "/RESET_MICO#") (class "Default")
      (node (ref "RA6") (pin "8") (pinfunction "8_8") (pintype "passive"))
      (node (ref "SW2") (pin "2") (pinfunction "2_2") (pintype "passive"))
      (node (ref "X5") (pin "6") (pinfunction "6_6") (pintype "passive"))
    )
    (net (code "35") (name "/RESET_MOCI") (class "Default")
      (node (ref "R25") (pin "1") (pinfunction "1_1") (pintype "passive"))
      (node (ref "T6") (pin "5") (pinfunction "G_5") (pintype "passive"))
      (node (ref "T6") (pin "6") (pinfunction "D_6") (pintype "passive"))
    )
    (net (code "36") (name "/RESET_MOCI#") (class "Default")
      (node (ref "IC4") (pin "1") (pinfunction "OE_1") (pintype "passive"))
      (node (ref "RA6") (pin "7") (pinfunction "7_7") (pintype "passive"))
      (node (ref "T6") (pin "2") (pinfunction "G_2") (pintype "passive"))
    )
    (net (code "37") (name "/RESET_MOCI_LED") (class "Default")
      (node (ref "LED2") (pin "1") (pinfunction "K_1") (pintype "passive"))
      (node (ref "T6") (pin "3") (pinfunction "D_3") (pintype "passive"))
    )
    (net (code "39") (name "/V_SUPPLY_SW_EN") (class "Default")
      (node (ref "C45") (pin "2") (pinfunction "2_2") (pintype "passive"))
      (node (ref "R32") (pin "2") (pinfunction "2_2") (pintype "passive"))
      (node (ref "T9") (pin "1") (pinfunction "1_1") (pintype "passive"))
    )
    (net (code "40") (name "/V_SUPPLY_SW_EN#") (class "Default")
      (node (ref "C43") (pin "1") (pinfunction "1_1") (pintype "passive"))
      (node (ref "D14") (pin "2") (pinfunction "A_2") (pintype "power_in"))
      (node (ref "R31") (pin "2") (pinfunction "2_2") (pintype "passive"))
      (node (ref "T8") (pin "4") (pinfunction "G_4") (pintype "passive"))
    )
    (net (code "41") (name "/V_SUPPLY_SW_EN_R") (class "Default")
      (node (ref "R30") (pin "1") (pinfunction "1_1") (pintype "passive"))
      (node (ref "R31") (pin "1") (pinfunction "1_1") (pintype "passive"))
      (node (ref "T9") (pin "3") (pinfunction "3_3") (pintype "passive"))
    )
    (net (code "42") (name "/WAKE1_MICO#") (class "Default")
      (node (ref "R146") (pin "1") (pinfunction "1_1") (pintype "passive"))
      (node (ref "RA6") (pin "5") (pinfunction "5_5") (pintype "passive"))
    )
    (net (code "43") (name "3.3V") (class "Default")
      (node (ref "C21") (pin "2") (pinfunction "2_2") (pintype "passive"))
      (node (ref "C22") (pin "2") (pinfunction "2_2") (pintype "passive"))
      (node (ref "C23") (pin "2") (pinfunction "2_2") (pintype "passive"))
      (node (ref "C24") (pin "2") (pinfunction "2_2") (pintype "passive"))
      (node (ref "C41") (pin "1") (pinfunction "1_1") (pintype "passive"))
      (node (ref "C42") (pin "2") (pinfunction "2_2") (pintype "passive"))
      (node (ref "IC2") (pin "8") (pinfunction "VO_8") (pintype "input"))
      (node (ref "IC4") (pin "5") (pinfunction "VCC_5") (pintype "passive"))
      (node (ref "L4") (pin "2") (pinfunction "2_2") (pintype "passive"))
      (node (ref "L6") (pin "1") (pinfunction "1_1") (pintype "passive"))
      (node (ref "R146") (pin "2") (pinfunction "2_2") (pintype "passive"))
      (node (ref "R18") (pin "1") (pinfunction "1_1") (pintype "passive"))
      (node (ref "R19") (pin "1") (pinfunction "1_1") (pintype "passive"))
      (node (ref "R20") (pin "2") (pinfunction "2_2") (pintype "passive"))
      (node (ref "R24") (pin "1") (pinfunction "1_1") (pintype "passive"))
      (node (ref "R25") (pin "2") (pinfunction "2_2") (pintype "passive"))
      (node (ref "R26") (pin "1") (pinfunction "1_1") (pintype "passive"))
      (node (ref "T5") (pin "1") (pinfunction "S_1") (pintype "passive"))
      (node (ref "T5") (pin "2") (pinfunction "S_2") (pintype "passive"))
      (node (ref "T5") (pin "3") (pinfunction "S_3") (pintype "passive"))
    )
    (net (code "44") (name "3.3V_SW") (class "Default")
      (node (ref "L6") (pin "2") (pinfunction "2_2") (pintype "passive"))
      (node (ref "R36") (pin "1") (pinfunction "1_1") (pintype "passive"))
      (node (ref "T5") (pin "5") (pinfunction "D_5") (pintype "passive"))
      (node (ref "T5") (pin "6") (pinfunction "D_6") (pintype "passive"))
      (node (ref "T5") (pin "7") (pinfunction "D_7") (pintype "passive"))
      (node (ref "T5") (pin "8") (pinfunction "D_8") (pintype "passive"))
    )
    (net (code "45") (name "5V_SW") (class "Default")
      (node (ref "C36") (pin "2") (pinfunction "2_2") (pintype "passive"))
      (node (ref "C37") (pin "2") (pinfunction "2_2") (pintype "passive"))
      (node (ref "C38") (pin "2") (pinfunction "2_2") (pintype "passive"))
      (node (ref "C39") (pin "2") (pinfunction "2_2") (pintype "passive"))
      (node (ref "IC2") (pin "1") (pinfunction "VO_1") (pintype "input"))
      (node (ref "L5") (pin "2") (pinfunction "2_2") (pintype "passive"))
    )
    (net (code "46") (name "GND") (class "Default")
      (node (ref "C14") (pin "1") (pinfunction "1_1") (pintype "passive"))
      (node (ref "C15") (pin "1") (pinfunction "1_1") (pintype "passive"))
      (node (ref "C16") (pin "1") (pinfunction "1_1") (pintype "passive"))
      (node (ref "C17") (pin "1") (pinfunction "1_1") (pintype "passive"))
      (node (ref "C18") (pin "1") (pinfunction "1_1") (pintype "passive"))
      (node (ref "C20") (pin "1") (pinfunction "1_1") (pintype "passive"))
      (node (ref "C21") (pin "1") (pinfunction "1_1") (pintype "passive"))
      (node (ref "C22") (pin "1") (pinfunction "1_1") (pintype "passive"))
      (node (ref "C23") (pin "1") (pinfunction "1_1") (pintype "passive"))
      (node (ref "C24") (pin "1") (pinfunction "1_1") (pintype "passive"))
      (node (ref "C25") (pin "1") (pinfunction "1_1") (pintype "passive"))
      (node (ref "C26") (pin "1") (pinfunction "1_1") (pintype "passive"))
      (node (ref "C27") (pin "1") (pinfunction "1_1") (pintype "passive"))
      (node (ref "C28") (pin "1") (pinfunction "1_1") (pintype "passive"))
      (node (ref "C29") (pin "1") (pinfunction "1_1") (pintype "passive"))
      (node (ref "C30") (pin "1") (pinfunction "1_1") (pintype "passive"))
      (node (ref "C31") (pin "1") (pinfunction "1_1") (pintype "passive"))
      (node (ref "C32") (pin "1") (pinfunction "1_1") (pintype "passive"))
      (node (ref "C34") (pin "1") (pinfunction "1_1") (pintype "passive"))
      (node (ref "C35") (pin "1") (pinfunction "1_1") (pintype "passive"))
      (node (ref "C36") (pin "1") (pinfunction "1_1") (pintype "passive"))
      (node (ref "C37") (pin "1") (pinfunction "1_1") (pintype "passive"))
      (node (ref "C38") (pin "1") (pinfunction "1_1") (pintype "passive"))
      (node (ref "C39") (pin "1") (pinfunction "1_1") (pintype "passive"))
      (node (ref "C40") (pin "1") (pinfunction "1_1") (pintype "passive"))
      (node (ref "C41") (pin "2") (pinfunction "2_2") (pintype "passive"))
      (node (ref "C44") (pin "1") (pinfunction "1_1") (pintype "passive"))
      (node (ref "C45") (pin "1") (pinfunction "1_1") (pintype "passive"))
      (node (ref "C47") (pin "1") (pinfunction "1_1") (pintype "passive"))
      (node (ref "IC1") (pin "2") (pinfunction "GND_2") (pintype "passive"))
      (node (ref "IC1") (pin "4") (pinfunction "GND_4") (pintype "passive"))
      (node (ref "IC2") (pin "17") (pinfunction "PGND_17") (pintype "power_in"))
      (node (ref "IC2") (pin "24") (pinfunction "PGND_24") (pintype "power_in"))
      (node (ref "IC2") (pin "32") (pinfunction "GND_32") (pintype "power_in"))
      (node (ref "IC2") (pin "33") (pinfunction "HS_33") (pintype "passive"))
      (node (ref "IC2") (pin "5") (pinfunction "GND_5") (pintype "power_in"))
      (node (ref "IC3") (pin "4") (pinfunction "GND_4") (pintype "passive"))
      (node (ref "IC4") (pin "3") (pinfunction "GND_3") (pintype "passive"))
      (node (ref "R13") (pin "1") (pinfunction "1_1") (pintype "passive"))
      (node (ref "R147") (pin "1") (pinfunction "1_1") (pintype "passive"))
      (node (ref "R21") (pin "2") (pinfunction "2_2") (pintype "passive"))
      (node (ref "R37") (pin "2") (pinfunction "2_2") (pintype "passive"))
      (node (ref "R7") (pin "1") (pinfunction "1_1") (pintype "passive"))
      (node (ref "R8") (pin "1") (pinfunction "1_1") (pintype "passive"))
      (node (ref "R9") (pin "2") (pinfunction "2_2") (pintype "passive"))
      (node (ref "SW1") (pin "1") (pinfunction "1_1") (pintype "passive"))
      (node (ref "SW1") (pin "3") (pinfunction "3_3") (pintype "passive"))
      (node (ref "SW2") (pin "1") (pinfunction "1_1") (pintype "passive"))
      (node (ref "SW2") (pin "3") (pinfunction "3_3") (pintype "passive"))
      (node (ref "T11") (pin "2") (pinfunction "2_2") (pintype "passive"))
      (node (ref "T3") (pin "1") (pinfunction "S_1") (pintype "passive"))
      (node (ref "T6") (pin "1") (pinfunction "S_1") (pintype "passive"))
      (node (ref "T6") (pin "4") (pinfunction "S_4") (pintype "passive"))
      (node (ref "T7") (pin "1") (pinfunction "S_1") (pintype "passive"))
      (node (ref "T9") (pin "2") (pinfunction "2_2") (pintype "passive"))
      (node (ref "X5") (pin "2") (pinfunction "2_2") (pintype "passive"))
      (node (ref "X6") (pin "1") (pinfunction "1_1") (pintype "passive"))
    )
    (net (code "47") (name "Net-(C29-Pad2)") (class "Default")
      (node (ref "C29") (pin "2") (pinfunction "2_2") (pintype "passive"))
      (node (ref "R10") (pin "1") (pinfunction "1_1") (pintype "passive"))
    )
    (net (code "48") (name "Net-(C40-Pad2)") (class "Default")
      (node (ref "C40") (pin "2") (pinfunction "2_2") (pintype "passive"))
      (node (ref "R22") (pin "1") (pinfunction "1_1") (pintype "passive"))
    )
    (net (code "49") (name "Net-(IC2A-TONSEL)") (class "Default")
      (node (ref "IC2") (pin "31") (pinfunction "TONSEL_31") (pintype "input"))
      (node (ref "R7") (pin "2") (pinfunction "2_2") (pintype "passive"))
    )
    (net (code "50") (name "Net-(IC2B-COMP)") (class "Default")
      (node (ref "IC2") (pin "2") (pinfunction "COMP_2") (pintype "output"))
      (node (ref "R22") (pin "2") (pinfunction "2_2") (pintype "passive"))
    )
    (net (code "51") (name "Net-(IC2B-CS)") (class "Default")
      (node (ref "IC2") (pin "23") (pinfunction "CS_23") (pintype "input"))
      (node (ref "R21") (pin "1") (pinfunction "1_1") (pintype "passive"))
      (node (ref "R23") (pin "1") (pinfunction "1_1") (pintype "passive"))
      (node (ref "T4") (pin "1") (pinfunction "S_1") (pintype "passive"))
    )
    (net (code "52") (name "Net-(IC2B-DRVH)") (class "Default")
      (node (ref "IC2") (pin "27") (pinfunction "DRVH_27") (pintype "output"))
      (node (ref "R16") (pin "1") (pinfunction "1_1") (pintype "passive"))
    )
    (net (code "53") (name "Net-(IC2B-DRVL)") (class "Default")
      (node (ref "IC2") (pin "25") (pinfunction "DRVL_25") (pintype "output"))
      (node (ref "T4") (pin "2") (pinfunction "G_2") (pintype "passive"))
    )
    (net (code "54") (name "Net-(IC2B-LL)") (class "Default")
      (node (ref "C33") (pin "1") (pinfunction "1_1") (pintype "passive"))
      (node (ref "IC2") (pin "26") (pinfunction "LL_26") (pintype "bidirectional"))
      (node (ref "L5") (pin "1") (pinfunction "1_1") (pintype "passive"))
      (node (ref "T4") (pin "3") (pinfunction "S_3") (pintype "passive"))
      (node (ref "T4") (pin "7") (pinfunction "D_7") (pintype "passive"))
      (node (ref "T4") (pin "8") (pinfunction "D_8") (pintype "passive"))
    )
    (net (code "55") (name "Net-(IC2B-VBST)") (class "Default")
      (node (ref "C33") (pin "2") (pinfunction "2_2") (pintype "passive"))
      (node (ref "IC2") (pin "28") (pinfunction "VBST_28") (pintype "power_in"))
    )
    (net (code "56") (name "Net-(IC2C-COMP)") (class "Default")
      (node (ref "IC2") (pin "7") (pinfunction "COMP_7") (pintype "output"))
      (node (ref "R10") (pin "2") (pinfunction "2_2") (pintype "passive"))
    )
    (net (code "57") (name "Net-(IC2C-CS)") (class "Default")
      (node (ref "IC2") (pin "18") (pinfunction "CS_18") (pintype "input"))
      (node (ref "R12") (pin "1") (pinfunction "1_1") (pintype "passive"))
      (node (ref "R9") (pin "1") (pinfunction "1_1") (pintype "passive"))
      (node (ref "T1") (pin "1") (pinfunction "S_1") (pintype "passive"))
    )
    (net (code "58") (name "Net-(IC2C-DRVH)") (class "Default")
      (node (ref "IC2") (pin "14") (pinfunction "DRVH_14") (pintype "output"))
      (node (ref "R4") (pin "1") (pinfunction "1_1") (pintype "passive"))
    )
    (net (code "59") (name "Net-(IC2C-DRVL)") (class "Default")
      (node (ref "IC2") (pin "16") (pinfunction "DRVL_16") (pintype "output"))
      (node (ref "T1") (pin "2") (pinfunction "G_2") (pintype "passive"))
    )
    (net (code "60") (name "Net-(IC2C-LL)") (class "Default")
      (node (ref "C19") (pin "1") (pinfunction "1_1") (pintype "passive"))
      (node (ref "IC2") (pin "15") (pinfunction "LL_15") (pintype "bidirectional"))
      (node (ref "L4") (pin "1") (pinfunction "1_1") (pintype "passive"))
      (node (ref "T1") (pin "3") (pinfunction "S_3") (pintype "passive"))
      (node (ref "T1") (pin "7") (pinfunction "D_7") (pintype "passive"))
      (node (ref "T1") (pin "8") (pinfunction "D_8") (pintype "passive"))
    )
    (net (code "61") (name "Net-(IC2C-PGOOD)") (class "Default")
      (node (ref "IC2") (pin "11") (pinfunction "PGOOD_11") (pintype "output"))
      (node (ref "R6") (pin "1") (pinfunction "1_1") (pintype "passive"))
    )
    (net (code "62") (name "Net-(IC2C-VBST)") (class "Default")
      (node (ref "C19") (pin "2") (pinfunction "2_2") (pintype "passive"))
      (node (ref "IC2") (pin "13") (pinfunction "VBST_13") (pintype "passive"))
    )
    (net (code "63") (name "Net-(IC3-ONT)") (class "Default")
      (node (ref "C34") (pin "2") (pinfunction "2_2") (pintype "passive"))
      (node (ref "IC3") (pin "3") (pinfunction "ONT_3") (pintype "passive"))
    )
    (net (code "64") (name "Net-(IC3-PDT)") (class "Default")
      (node (ref "C35") (pin "2") (pinfunction "2_2") (pintype "passive"))
      (node (ref "IC3") (pin "7") (pinfunction "PDT_7") (pintype "passive"))
    )
    (net (code "65") (name "Net-(LED2-A)") (class "Default")
      (node (ref "LED2") (pin "2") (pinfunction "A_2") (pintype "passive"))
      (node (ref "R24") (pin "2") (pinfunction "2_2") (pintype "passive"))
    )
    (net (code "66") (name "Net-(T1B-G)") (class "Default")
      (node (ref "R4") (pin "2") (pinfunction "2_2") (pintype "passive"))
      (node (ref "T1") (pin "4") (pinfunction "G_4") (pintype "passive"))
    )
    (net (code "67") (name "Net-(T4B-G)") (class "Default")
      (node (ref "R16") (pin "2") (pinfunction "2_2") (pintype "passive"))
      (node (ref "T4") (pin "4") (pinfunction "G_4") (pintype "passive"))
    )
    (net (code "68") (name "SHIELD2") (class "Default")
      (node (ref "SW1") (pin "SH1") (pinfunction "SH1_SH1") (pintype "passive"))
      (node (ref "SW1") (pin "SH2") (pinfunction "SH2_SH2") (pintype "passive"))
      (node (ref "SW2") (pin "SH1") (pinfunction "SH1_SH1") (pintype "passive"))
      (node (ref "SW2") (pin "SH2") (pinfunction "SH2_SH2") (pintype "passive"))
    )
    (net (code "69") (name "V5FILT") (class "Default")
      (node (ref "C20") (pin "2") (pinfunction "2_2") (pintype "passive"))
      (node (ref "IC2") (pin "20") (pinfunction "V5FILT_20") (pintype "power_in"))
      (node (ref "IC2") (pin "3") (pinfunction "VFB_3") (pintype "input"))
      (node (ref "IC2") (pin "6") (pinfunction "VFB_6") (pintype "input"))
      (node (ref "R12") (pin "2") (pinfunction "2_2") (pintype "passive"))
      (node (ref "R17") (pin "2") (pinfunction "2_2") (pintype "passive"))
      (node (ref "R23") (pin "2") (pinfunction "2_2") (pintype "passive"))
      (node (ref "R5") (pin "1") (pinfunction "1_1") (pintype "passive"))
      (node (ref "R6") (pin "2") (pinfunction "2_2") (pintype "passive"))
    )
    (net (code "70") (name "VREF2") (class "Default")
      (node (ref "C28") (pin "2") (pinfunction "2_2") (pintype "passive"))
      (node (ref "IC2") (pin "4") (pinfunction "VREF2_4") (pintype "output"))
    )
    (net (code "71") (name "VREG3") (class "Default")
      (node (ref "C25") (pin "2") (pinfunction "2_2") (pintype "passive"))
      (node (ref "IC2") (pin "19") (pinfunction "VREG3_19") (pintype "output"))
    )
    (net (code "72") (name "VREG5") (class "Default")
      (node (ref "C14") (pin "2") (pinfunction "2_2") (pintype "passive"))
      (node (ref "IC2") (pin "10") (pinfunction "EN3_10") (pintype "input"))
      (node (ref "IC2") (pin "21") (pinfunction "VREG5_21") (pintype "output"))
      (node (ref "R5") (pin "2") (pinfunction "2_2") (pintype "passive"))
    )
    (net (code "73") (name "VSTB") (class "Default")
      (node (ref "C18") (pin "2") (pinfunction "2_2") (pintype "passive"))
      (node (ref "C32") (pin "2") (pinfunction "2_2") (pintype "passive"))
      (node (ref "IC1") (pin "3") (pinfunction "Vout_3") (pintype "passive"))
      (node (ref "IC3") (pin "1") (pinfunction "Vin_1") (pintype "passive"))
      (node (ref "JP1") (pin "2") (pinfunction "2_2") (pintype "passive"))
      (node (ref "R11") (pin "2") (pinfunction "2_2") (pintype "passive"))
      (node (ref "T2") (pin "2") (pinfunction "2_2") (pintype "passive"))
    )
    (net (code "74") (name "V_FAN_UNREG") (class "Default")
      (node (ref "C47") (pin "2") (pinfunction "2_2") (pintype "passive"))
      (node (ref "R68") (pin "2") (pinfunction "2_2") (pintype "passive"))
      (node (ref "T10") (pin "5") (pinfunction "D_5") (pintype "passive"))
      (node (ref "T10") (pin "6") (pinfunction "D_6") (pintype "passive"))
      (node (ref "T10") (pin "7") (pinfunction "D_7") (pintype "passive"))
      (node (ref "T10") (pin "8") (pinfunction "D_8") (pintype "passive"))
      (node (ref "X6") (pin "2") (pinfunction "2_2") (pintype "passive"))
    )
    (net (code "75") (name "V_SUPPLY_FILT") (class "Default")
      (node (ref "C15") (pin "2") (pinfunction "2_2") (pintype "passive"))
      (node (ref "C16") (pin "2") (pinfunction "2_2") (pintype "passive"))
      (node (ref "C17") (pin "2") (pinfunction "2_2") (pintype "passive"))
      (node (ref "C26") (pin "2") (pinfunction "2_2") (pintype "passive"))
      (node (ref "C30") (pin "2") (pinfunction "2_2") (pintype "passive"))
      (node (ref "C31") (pin "2") (pinfunction "2_2") (pintype "passive"))
      (node (ref "C43") (pin "2") (pinfunction "2_2") (pintype "passive"))
      (node (ref "C46") (pin "2") (pinfunction "2_2") (pintype "passive"))
      (node (ref "D14") (pin "1") (pinfunction "C_1") (pintype "power_in"))
      (node (ref "D16") (pin "1") (pinfunction "C_1") (pintype "power_in"))
      (node (ref "IC1") (pin "1") (pinfunction "Vin_1") (pintype "passive"))
      (node (ref "IC2") (pin "22") (pinfunction "VIN_22") (pintype "power_in"))
      (node (ref "L7") (pin "1") (pinfunction "1_1") (pintype "passive"))
      (node (ref "R30") (pin "2") (pinfunction "2_2") (pintype "passive"))
      (node (ref "R33") (pin "2") (pinfunction "2_2") (pintype "passive"))
      (node (ref "R68") (pin "1") (pinfunction "1_1") (pintype "passive"))
      (node (ref "T1") (pin "5") (pinfunction "D_5") (pintype "passive"))
      (node (ref "T1") (pin "6") (pinfunction "D_6") (pintype "passive"))
      (node (ref "T10") (pin "1") (pinfunction "S_1") (pintype "passive"))
      (node (ref "T10") (pin "2") (pinfunction "S_2") (pintype "passive"))
      (node (ref "T10") (pin "3") (pinfunction "S_3") (pintype "passive"))
      (node (ref "T4") (pin "5") (pinfunction "D_5") (pintype "passive"))
      (node (ref "T4") (pin "6") (pinfunction "D_6") (pintype "passive"))
      (node (ref "T8") (pin "1") (pinfunction "S_1") (pintype "passive"))
      (node (ref "T8") (pin "2") (pinfunction "S_2") (pintype "passive"))
      (node (ref "T8") (pin "3") (pinfunction "S_3") (pintype "passive"))
    )
    (net (code "76") (name "V_SUPPLY_FILT_SW") (class "Default")
      (node (ref "C44") (pin "2") (pinfunction "2_2") (pintype "passive"))
      (node (ref "L7") (pin "2") (pinfunction "2_2") (pintype "passive"))
      (node (ref "T8") (pin "5") (pinfunction "D_5") (pintype "passive"))
      (node (ref "T8") (pin "6") (pinfunction "D_6") (pintype "passive"))
      (node (ref "T8") (pin "7") (pinfunction "D_7") (pintype "passive"))
      (node (ref "T8") (pin "8") (pinfunction "D_8") (pintype "passive"))
    )
    (net (code "77") (name "unconnected-(T3B-D-Pad3)") (class "Default")
      (node (ref "T3") (pin "3") (pinfunction "D_3") (pintype "passive+no_connect"))
    )
    (net (code "78") (name "unconnected-(T3B-G-Pad5)") (class "Default")
      (node (ref "T3") (pin "5") (pinfunction "G_5") (pintype "passive+no_connect"))
    )
    (net (code "79") (name "unconnected-(T3B-S-Pad4)") (class "Default")
      (node (ref "T3") (pin "4") (pinfunction "S_4") (pintype "passive+no_connect"))
    )
    (net (code "80") (name "unconnected-(T7B-D-Pad3)") (class "Default")
      (node (ref "T7") (pin "3") (pinfunction "D_3") (pintype "passive+no_connect"))
    )
    (net (code "81") (name "unconnected-(T7B-G-Pad5)") (class "Default")
      (node (ref "T7") (pin "5") (pinfunction "G_5") (pintype "passive+no_connect"))
    )
    (net (code "82") (name "unconnected-(T7B-S-Pad4)") (class "Default")
      (node (ref "T7") (pin "4") (pinfunction "S_4") (pintype "passive+no_connect"))
    )
    (net (code "83") (name "unconnected-(X6-Pad3)") (class "Default")
      (node (ref "X6") (pin "3") (pinfunction "3_3") (pintype "passive+no_connect"))
    )
  )
)
